# BMS_Adapter_Segment_rev1.net
KiCad netlist of a schematic drawn in EAGLE
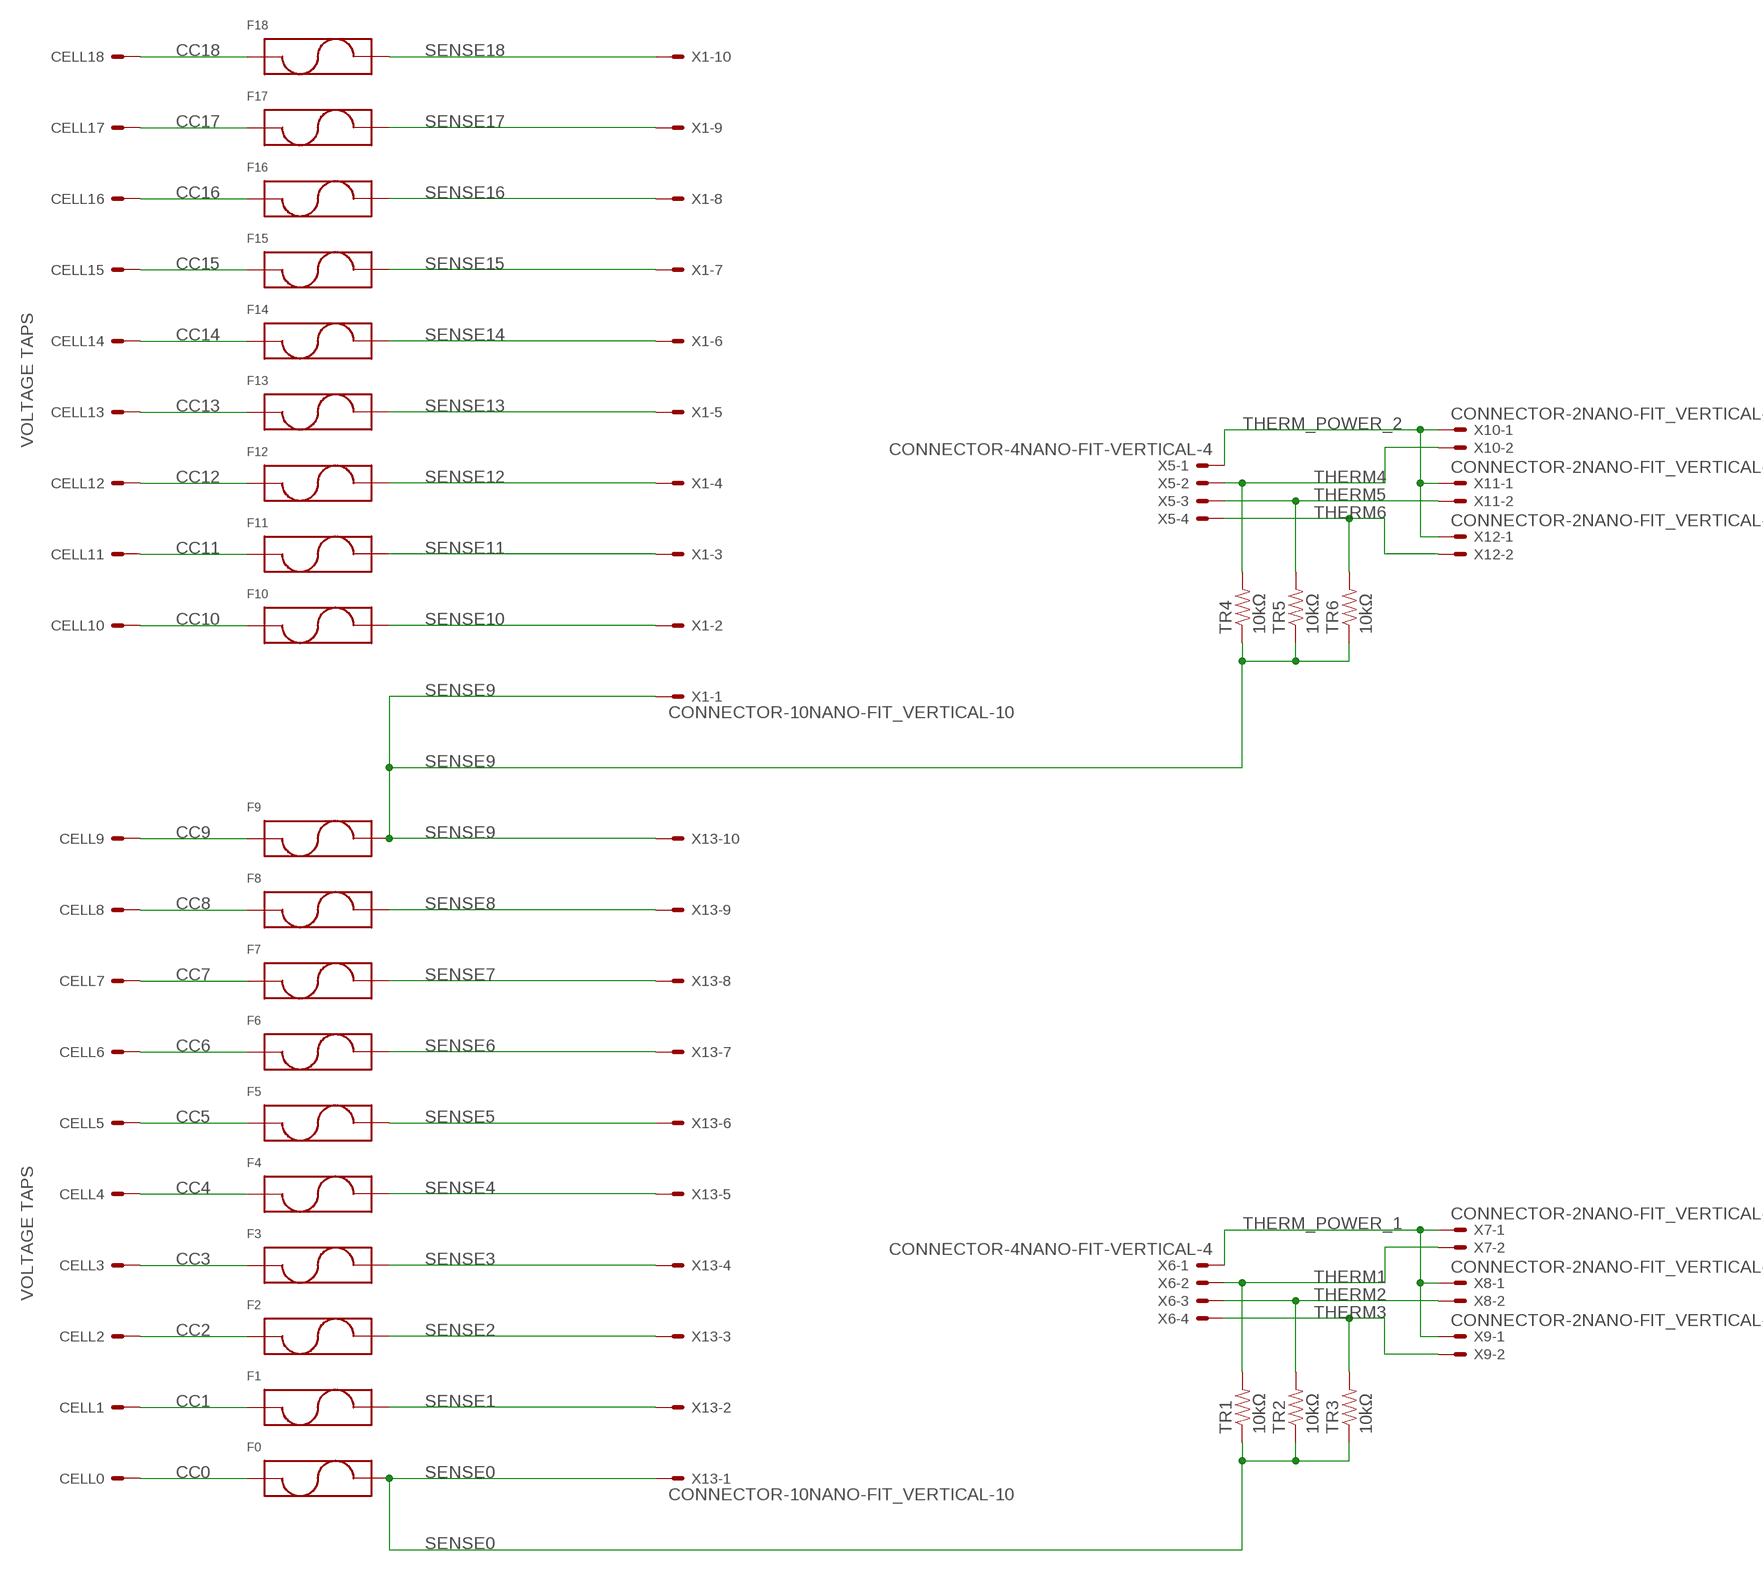
[diagram p0: schematic, sheet 1]

(export (version "E")
  (design (tool "Eeschema 10.0.6"))
  (components
    (comp (ref "CELL0")
      (value "BATTERY_SPRING_KEYSTONE5222")
      (footprint "eagle-import:KEYSTONE5222")
      (libsource (lib "eagle-import") (part "BATTERY_SPRING_KEYSTONE5222"))
    )
    (comp (ref "CELL1")
      (value "BATTERY_SPRING_KEYSTONE5222")
      (footprint "eagle-import:KEYSTONE5222")
      (libsource (lib "eagle-import") (part "BATTERY_SPRING_KEYSTONE5222"))
    )
    (comp (ref "CELL2")
      (value "BATTERY_SPRING_KEYSTONE5222")
      (footprint "eagle-import:KEYSTONE5222")
      (libsource (lib "eagle-import") (part "BATTERY_SPRING_KEYSTONE5222"))
    )
    (comp (ref "CELL3")
      (value "BATTERY_SPRING_KEYSTONE5222")
      (footprint "eagle-import:KEYSTONE5222")
      (libsource (lib "eagle-import") (part "BATTERY_SPRING_KEYSTONE5222"))
    )
    (comp (ref "CELL4")
      (value "BATTERY_SPRING_KEYSTONE5222")
      (footprint "eagle-import:KEYSTONE5222")
      (libsource (lib "eagle-import") (part "BATTERY_SPRING_KEYSTONE5222"))
    )
    (comp (ref "CELL5")
      (value "BATTERY_SPRING_KEYSTONE5222")
      (footprint "eagle-import:KEYSTONE5222")
      (libsource (lib "eagle-import") (part "BATTERY_SPRING_KEYSTONE5222"))
    )
    (comp (ref "CELL6")
      (value "BATTERY_SPRING_KEYSTONE5222")
      (footprint "eagle-import:KEYSTONE5222")
      (libsource (lib "eagle-import") (part "BATTERY_SPRING_KEYSTONE5222"))
    )
    (comp (ref "CELL7")
      (value "BATTERY_SPRING_KEYSTONE5222")
      (footprint "eagle-import:KEYSTONE5222")
      (libsource (lib "eagle-import") (part "BATTERY_SPRING_KEYSTONE5222"))
    )
    (comp (ref "CELL8")
      (value "BATTERY_SPRING_KEYSTONE5222")
      (footprint "eagle-import:KEYSTONE5222")
      (libsource (lib "eagle-import") (part "BATTERY_SPRING_KEYSTONE5222"))
    )
    (comp (ref "CELL9")
      (value "BATTERY_SPRING_KEYSTONE5222")
      (footprint "eagle-import:KEYSTONE5222")
      (libsource (lib "eagle-import") (part "BATTERY_SPRING_KEYSTONE5222"))
    )
    (comp (ref "CELL10")
      (value "BATTERY_SPRING_KEYSTONE5222")
      (footprint "eagle-import:KEYSTONE5222")
      (libsource (lib "eagle-import") (part "BATTERY_SPRING_KEYSTONE5222"))
    )
    (comp (ref "CELL11")
      (value "BATTERY_SPRING_KEYSTONE5222")
      (footprint "eagle-import:KEYSTONE5222")
      (libsource (lib "eagle-import") (part "BATTERY_SPRING_KEYSTONE5222"))
    )
    (comp (ref "CELL12")
      (value "BATTERY_SPRING_KEYSTONE5222")
      (footprint "eagle-import:KEYSTONE5222")
      (libsource (lib "eagle-import") (part "BATTERY_SPRING_KEYSTONE5222"))
    )
    (comp (ref "CELL13")
      (value "BATTERY_SPRING_KEYSTONE5222")
      (footprint "eagle-import:KEYSTONE5222")
      (libsource (lib "eagle-import") (part "BATTERY_SPRING_KEYSTONE5222"))
    )
    (comp (ref "CELL14")
      (value "BATTERY_SPRING_KEYSTONE5222")
      (footprint "eagle-import:KEYSTONE5222")
      (libsource (lib "eagle-import") (part "BATTERY_SPRING_KEYSTONE5222"))
    )
    (comp (ref "CELL15")
      (value "BATTERY_SPRING_KEYSTONE5222")
      (footprint "eagle-import:KEYSTONE5222")
      (libsource (lib "eagle-import") (part "BATTERY_SPRING_KEYSTONE5222"))
    )
    (comp (ref "CELL16")
      (value "BATTERY_SPRING_KEYSTONE5222")
      (footprint "eagle-import:KEYSTONE5222")
      (libsource (lib "eagle-import") (part "BATTERY_SPRING_KEYSTONE5222"))
    )
    (comp (ref "CELL17")
      (value "BATTERY_SPRING_KEYSTONE5222")
      (footprint "eagle-import:KEYSTONE5222")
      (libsource (lib "eagle-import") (part "BATTERY_SPRING_KEYSTONE5222"))
    )
    (comp (ref "CELL18")
      (value "BATTERY_SPRING_KEYSTONE5222")
      (footprint "eagle-import:KEYSTONE5222")
      (libsource (lib "eagle-import") (part "BATTERY_SPRING_KEYSTONE5222"))
    )
    (comp (ref "F0")
      (value "FUSE_OMF_250")
      (footprint "eagle-import:OMF_250")
      (libsource (lib "eagle-import") (part "FUSE_OMF_250"))
    )
    (comp (ref "F1")
      (value "FUSE_OMF_250")
      (footprint "eagle-import:OMF_250")
      (libsource (lib "eagle-import") (part "FUSE_OMF_250"))
    )
    (comp (ref "F2")
      (value "FUSE_OMF_250")
      (footprint "eagle-import:OMF_250")
      (libsource (lib "eagle-import") (part "FUSE_OMF_250"))
    )
    (comp (ref "F3")
      (value "FUSE_OMF_250")
      (footprint "eagle-import:OMF_250")
      (libsource (lib "eagle-import") (part "FUSE_OMF_250"))
    )
    (comp (ref "F4")
      (value "FUSE_OMF_250")
      (footprint "eagle-import:OMF_250")
      (libsource (lib "eagle-import") (part "FUSE_OMF_250"))
    )
    (comp (ref "F5")
      (value "FUSE_OMF_250")
      (footprint "eagle-import:OMF_250")
      (libsource (lib "eagle-import") (part "FUSE_OMF_250"))
    )
    (comp (ref "F6")
      (value "FUSE_OMF_250")
      (footprint "eagle-import:OMF_250")
      (libsource (lib "eagle-import") (part "FUSE_OMF_250"))
    )
    (comp (ref "F7")
      (value "FUSE_OMF_250")
      (footprint "eagle-import:OMF_250")
      (libsource (lib "eagle-import") (part "FUSE_OMF_250"))
    )
    (comp (ref "F8")
      (value "FUSE_OMF_250")
      (footprint "eagle-import:OMF_250")
      (libsource (lib "eagle-import") (part "FUSE_OMF_250"))
    )
    (comp (ref "F9")
      (value "FUSE_OMF_250")
      (footprint "eagle-import:OMF_250")
      (libsource (lib "eagle-import") (part "FUSE_OMF_250"))
    )
    (comp (ref "F10")
      (value "FUSE_OMF_250")
      (footprint "eagle-import:OMF_250")
      (libsource (lib "eagle-import") (part "FUSE_OMF_250"))
    )
    (comp (ref "F11")
      (value "FUSE_OMF_250")
      (footprint "eagle-import:OMF_250")
      (libsource (lib "eagle-import") (part "FUSE_OMF_250"))
    )
    (comp (ref "F12")
      (value "FUSE_OMF_250")
      (footprint "eagle-import:OMF_250")
      (libsource (lib "eagle-import") (part "FUSE_OMF_250"))
    )
    (comp (ref "F13")
      (value "FUSE_OMF_250")
      (footprint "eagle-import:OMF_250")
      (libsource (lib "eagle-import") (part "FUSE_OMF_250"))
    )
    (comp (ref "F14")
      (value "FUSE_OMF_250")
      (footprint "eagle-import:OMF_250")
      (libsource (lib "eagle-import") (part "FUSE_OMF_250"))
    )
    (comp (ref "F15")
      (value "FUSE_OMF_250")
      (footprint "eagle-import:OMF_250")
      (libsource (lib "eagle-import") (part "FUSE_OMF_250"))
    )
    (comp (ref "F16")
      (value "FUSE_OMF_250")
      (footprint "eagle-import:OMF_250")
      (libsource (lib "eagle-import") (part "FUSE_OMF_250"))
    )
    (comp (ref "F17")
      (value "FUSE_OMF_250")
      (footprint "eagle-import:OMF_250")
      (libsource (lib "eagle-import") (part "FUSE_OMF_250"))
    )
    (comp (ref "F18")
      (value "FUSE_OMF_250")
      (footprint "eagle-import:OMF_250")
      (libsource (lib "eagle-import") (part "FUSE_OMF_250"))
    )
    (comp (ref "TR1")
      (value "10kΩ")
      (footprint "eagle-import:0805")
      (libsource (lib "eagle-import") (part "RESISTOR0805-RES"))
    )
    (comp (ref "TR2")
      (value "10kΩ")
      (footprint "eagle-import:0805")
      (libsource (lib "eagle-import") (part "RESISTOR0805-RES"))
    )
    (comp (ref "TR3")
      (value "10kΩ")
      (footprint "eagle-import:0805")
      (libsource (lib "eagle-import") (part "RESISTOR0805-RES"))
    )
    (comp (ref "TR4")
      (value "10kΩ")
      (footprint "eagle-import:0805")
      (libsource (lib "eagle-import") (part "RESISTOR0805-RES"))
    )
    (comp (ref "TR5")
      (value "10kΩ")
      (footprint "eagle-import:0805")
      (libsource (lib "eagle-import") (part "RESISTOR0805-RES"))
    )
    (comp (ref "TR6")
      (value "10kΩ")
      (footprint "eagle-import:0805")
      (libsource (lib "eagle-import") (part "RESISTOR0805-RES"))
    )
    (comp (ref "X1")
      (value "CONNECTOR-10NANO-FIT_VERTICAL-10")
      (footprint "eagle-import:NANO-FIT_VERTICAL-10")
      (libsource (lib "eagle-import") (part "CONNECTOR-10NANO-FIT_VERTICAL-10"))
    )
    (comp (ref "X5")
      (value "CONNECTOR-4NANO-FIT-VERTICAL-4")
      (footprint "eagle-import:NANO-FIT_VERTICAL-4")
      (libsource (lib "eagle-import") (part "CONNECTOR-4NANO-FIT-VERTICAL-4"))
    )
    (comp (ref "X6")
      (value "CONNECTOR-4NANO-FIT-VERTICAL-4")
      (footprint "eagle-import:NANO-FIT_VERTICAL-4")
      (libsource (lib "eagle-import") (part "CONNECTOR-4NANO-FIT-VERTICAL-4"))
    )
    (comp (ref "X7")
      (value "CONNECTOR-2NANO-FIT_VERTICAL-2")
      (footprint "eagle-import:NANO-FIT_VERTICAL-2")
      (libsource (lib "eagle-import") (part "CONNECTOR-2NANO-FIT_VERTICAL-2"))
    )
    (comp (ref "X8")
      (value "CONNECTOR-2NANO-FIT_VERTICAL-2")
      (footprint "eagle-import:NANO-FIT_VERTICAL-2")
      (libsource (lib "eagle-import") (part "CONNECTOR-2NANO-FIT_VERTICAL-2"))
    )
    (comp (ref "X9")
      (value "CONNECTOR-2NANO-FIT_VERTICAL-2")
      (footprint "eagle-import:NANO-FIT_VERTICAL-2")
      (libsource (lib "eagle-import") (part "CONNECTOR-2NANO-FIT_VERTICAL-2"))
    )
    (comp (ref "X10")
      (value "CONNECTOR-2NANO-FIT_VERTICAL-2")
      (footprint "eagle-import:NANO-FIT_VERTICAL-2")
      (libsource (lib "eagle-import") (part "CONNECTOR-2NANO-FIT_VERTICAL-2"))
    )
    (comp (ref "X11")
      (value "CONNECTOR-2NANO-FIT_VERTICAL-2")
      (footprint "eagle-import:NANO-FIT_VERTICAL-2")
      (libsource (lib "eagle-import") (part "CONNECTOR-2NANO-FIT_VERTICAL-2"))
    )
    (comp (ref "X12")
      (value "CONNECTOR-2NANO-FIT_VERTICAL-2")
      (footprint "eagle-import:NANO-FIT_VERTICAL-2")
      (libsource (lib "eagle-import") (part "CONNECTOR-2NANO-FIT_VERTICAL-2"))
    )
    (comp (ref "X13")
      (value "CONNECTOR-10NANO-FIT_VERTICAL-10")
      (footprint "eagle-import:NANO-FIT_VERTICAL-10")
      (libsource (lib "eagle-import") (part "CONNECTOR-10NANO-FIT_VERTICAL-10"))
    )
  )
  (nets
    (net (code "1") (name "/CC0") (class "Default")
      (node (ref "CELL0") (pin "P$1") (pinfunction "S_P$1") (pintype "passive"))
      (node (ref "F0") (pin "P$1") (pinfunction "P1_P$1") (pintype "bidirectional"))
    )
    (net (code "2") (name "/CC1") (class "Default")
      (node (ref "CELL1") (pin "P$1") (pinfunction "S_P$1") (pintype "passive"))
      (node (ref "F1") (pin "P$1") (pinfunction "P1_P$1") (pintype "bidirectional"))
    )
    (net (code "3") (name "/CC2") (class "Default")
      (node (ref "CELL2") (pin "P$1") (pinfunction "S_P$1") (pintype "passive"))
      (node (ref "F2") (pin "P$1") (pinfunction "P1_P$1") (pintype "bidirectional"))
    )
    (net (code "4") (name "/CC3") (class "Default")
      (node (ref "CELL3") (pin "P$1") (pinfunction "S_P$1") (pintype "passive"))
      (node (ref "F3") (pin "P$1") (pinfunction "P1_P$1") (pintype "bidirectional"))
    )
    (net (code "5") (name "/CC4") (class "Default")
      (node (ref "CELL4") (pin "P$1") (pinfunction "S_P$1") (pintype "passive"))
      (node (ref "F4") (pin "P$1") (pinfunction "P1_P$1") (pintype "bidirectional"))
    )
    (net (code "6") (name "/CC5") (class "Default")
      (node (ref "CELL5") (pin "P$1") (pinfunction "S_P$1") (pintype "passive"))
      (node (ref "F5") (pin "P$1") (pinfunction "P1_P$1") (pintype "bidirectional"))
    )
    (net (code "7") (name "/CC6") (class "Default")
      (node (ref "CELL6") (pin "P$1") (pinfunction "S_P$1") (pintype "passive"))
      (node (ref "F6") (pin "P$1") (pinfunction "P1_P$1") (pintype "bidirectional"))
    )
    (net (code "8") (name "/CC7") (class "Default")
      (node (ref "CELL7") (pin "P$1") (pinfunction "S_P$1") (pintype "passive"))
      (node (ref "F7") (pin "P$1") (pinfunction "P1_P$1") (pintype "bidirectional"))
    )
    (net (code "9") (name "/CC8") (class "Default")
      (node (ref "CELL8") (pin "P$1") (pinfunction "S_P$1") (pintype "passive"))
      (node (ref "F8") (pin "P$1") (pinfunction "P1_P$1") (pintype "bidirectional"))
    )
    (net (code "10") (name "/CC9") (class "Default")
      (node (ref "CELL9") (pin "P$1") (pinfunction "S_P$1") (pintype "passive"))
      (node (ref "F9") (pin "P$1") (pinfunction "P1_P$1") (pintype "bidirectional"))
    )
    (net (code "11") (name "/CC10") (class "Default")
      (node (ref "CELL10") (pin "P$1") (pinfunction "S_P$1") (pintype "passive"))
      (node (ref "F10") (pin "P$1") (pinfunction "P1_P$1") (pintype "bidirectional"))
    )
    (net (code "12") (name "/CC11") (class "Default")
      (node (ref "CELL11") (pin "P$1") (pinfunction "S_P$1") (pintype "passive"))
      (node (ref "F11") (pin "P$1") (pinfunction "P1_P$1") (pintype "bidirectional"))
    )
    (net (code "13") (name "/CC12") (class "Default")
      (node (ref "CELL12") (pin "P$1") (pinfunction "S_P$1") (pintype "passive"))
      (node (ref "F12") (pin "P$1") (pinfunction "P1_P$1") (pintype "bidirectional"))
    )
    (net (code "14") (name "/CC13") (class "Default")
      (node (ref "CELL13") (pin "P$1") (pinfunction "S_P$1") (pintype "passive"))
      (node (ref "F13") (pin "P$1") (pinfunction "P1_P$1") (pintype "bidirectional"))
    )
    (net (code "15") (name "/CC14") (class "Default")
      (node (ref "CELL14") (pin "P$1") (pinfunction "S_P$1") (pintype "passive"))
      (node (ref "F14") (pin "P$1") (pinfunction "P1_P$1") (pintype "bidirectional"))
    )
    (net (code "16") (name "/CC15") (class "Default")
      (node (ref "CELL15") (pin "P$1") (pinfunction "S_P$1") (pintype "passive"))
      (node (ref "F15") (pin "P$1") (pinfunction "P1_P$1") (pintype "bidirectional"))
    )
    (net (code "17") (name "/CC16") (class "Default")
      (node (ref "CELL16") (pin "P$1") (pinfunction "S_P$1") (pintype "passive"))
      (node (ref "F16") (pin "P$1") (pinfunction "P1_P$1") (pintype "bidirectional"))
    )
    (net (code "18") (name "/CC17") (class "Default")
      (node (ref "CELL17") (pin "P$1") (pinfunction "S_P$1") (pintype "passive"))
      (node (ref "F17") (pin "P$1") (pinfunction "P1_P$1") (pintype "bidirectional"))
    )
    (net (code "19") (name "/CC18") (class "Default")
      (node (ref "CELL18") (pin "P$1") (pinfunction "S_P$1") (pintype "passive"))
      (node (ref "F18") (pin "P$1") (pinfunction "P1_P$1") (pintype "bidirectional"))
    )
    (net (code "20") (name "/SENSE0") (class "Default")
      (node (ref "F0") (pin "P$2") (pinfunction "P2_P$2") (pintype "bidirectional"))
      (node (ref "TR1") (pin "1") (pinfunction "1_1") (pintype "passive"))
      (node (ref "TR2") (pin "1") (pinfunction "1_1") (pintype "passive"))
      (node (ref "TR3") (pin "1") (pinfunction "1_1") (pintype "passive"))
      (node (ref "X13") (pin "P$1") (pinfunction "S_P$1") (pintype "passive"))
    )
    (net (code "21") (name "/SENSE1") (class "Default")
      (node (ref "F1") (pin "P$2") (pinfunction "P2_P$2") (pintype "bidirectional"))
      (node (ref "X13") (pin "P$2") (pinfunction "S_P$2") (pintype "passive"))
    )
    (net (code "22") (name "/SENSE2") (class "Default")
      (node (ref "F2") (pin "P$2") (pinfunction "P2_P$2") (pintype "bidirectional"))
      (node (ref "X13") (pin "P$3") (pinfunction "S_P$3") (pintype "passive"))
    )
    (net (code "23") (name "/SENSE3") (class "Default")
      (node (ref "F3") (pin "P$2") (pinfunction "P2_P$2") (pintype "bidirectional"))
      (node (ref "X13") (pin "P$4") (pinfunction "S_P$4") (pintype "passive"))
    )
    (net (code "24") (name "/SENSE4") (class "Default")
      (node (ref "F4") (pin "P$2") (pinfunction "P2_P$2") (pintype "bidirectional"))
      (node (ref "X13") (pin "P$5") (pinfunction "S_P$5") (pintype "passive"))
    )
    (net (code "25") (name "/SENSE5") (class "Default")
      (node (ref "F5") (pin "P$2") (pinfunction "P2_P$2") (pintype "bidirectional"))
      (node (ref "X13") (pin "P$6") (pinfunction "S_P$6") (pintype "passive"))
    )
    (net (code "26") (name "/SENSE6") (class "Default")
      (node (ref "F6") (pin "P$2") (pinfunction "P2_P$2") (pintype "bidirectional"))
      (node (ref "X13") (pin "P$7") (pinfunction "S_P$7") (pintype "passive"))
    )
    (net (code "27") (name "/SENSE7") (class "Default")
      (node (ref "F7") (pin "P$2") (pinfunction "P2_P$2") (pintype "bidirectional"))
      (node (ref "X13") (pin "P$8") (pinfunction "S_P$8") (pintype "passive"))
    )
    (net (code "28") (name "/SENSE8") (class "Default")
      (node (ref "F8") (pin "P$2") (pinfunction "P2_P$2") (pintype "bidirectional"))
      (node (ref "X13") (pin "P$9") (pinfunction "S_P$9") (pintype "passive"))
    )
    (net (code "29") (name "/SENSE9") (class "Default")
      (node (ref "F9") (pin "P$2") (pinfunction "P2_P$2") (pintype "bidirectional"))
      (node (ref "TR4") (pin "1") (pinfunction "1_1") (pintype "passive"))
      (node (ref "TR5") (pin "1") (pinfunction "1_1") (pintype "passive"))
      (node (ref "TR6") (pin "1") (pinfunction "1_1") (pintype "passive"))
      (node (ref "X1") (pin "P$1") (pinfunction "S_P$1") (pintype "passive"))
      (node (ref "X13") (pin "P$10") (pinfunction "S_P$10") (pintype "passive"))
    )
    (net (code "30") (name "/SENSE10") (class "Default")
      (node (ref "F10") (pin "P$2") (pinfunction "P2_P$2") (pintype "bidirectional"))
      (node (ref "X1") (pin "P$2") (pinfunction "S_P$2") (pintype "passive"))
    )
    (net (code "31") (name "/SENSE11") (class "Default")
      (node (ref "F11") (pin "P$2") (pinfunction "P2_P$2") (pintype "bidirectional"))
      (node (ref "X1") (pin "P$3") (pinfunction "S_P$3") (pintype "passive"))
    )
    (net (code "32") (name "/SENSE12") (class "Default")
      (node (ref "F12") (pin "P$2") (pinfunction "P2_P$2") (pintype "bidirectional"))
      (node (ref "X1") (pin "P$4") (pinfunction "S_P$4") (pintype "passive"))
    )
    (net (code "33") (name "/SENSE13") (class "Default")
      (node (ref "F13") (pin "P$2") (pinfunction "P2_P$2") (pintype "bidirectional"))
      (node (ref "X1") (pin "P$5") (pinfunction "S_P$5") (pintype "passive"))
    )
    (net (code "34") (name "/SENSE14") (class "Default")
      (node (ref "F14") (pin "P$2") (pinfunction "P2_P$2") (pintype "bidirectional"))
      (node (ref "X1") (pin "P$6") (pinfunction "S_P$6") (pintype "passive"))
    )
    (net (code "35") (name "/SENSE15") (class "Default")
      (node (ref "F15") (pin "P$2") (pinfunction "P2_P$2") (pintype "bidirectional"))
      (node (ref "X1") (pin "P$7") (pinfunction "S_P$7") (pintype "passive"))
    )
    (net (code "36") (name "/SENSE16") (class "Default")
      (node (ref "F16") (pin "P$2") (pinfunction "P2_P$2") (pintype "bidirectional"))
      (node (ref "X1") (pin "P$8") (pinfunction "S_P$8") (pintype "passive"))
    )
    (net (code "37") (name "/SENSE17") (class "Default")
      (node (ref "F17") (pin "P$2") (pinfunction "P2_P$2") (pintype "bidirectional"))
      (node (ref "X1") (pin "P$9") (pinfunction "S_P$9") (pintype "passive"))
    )
    (net (code "38") (name "/SENSE18") (class "Default")
      (node (ref "F18") (pin "P$2") (pinfunction "P2_P$2") (pintype "bidirectional"))
      (node (ref "X1") (pin "P$10") (pinfunction "S_P$10") (pintype "passive"))
    )
    (net (code "39") (name "/THERM1") (class "Default")
      (node (ref "TR1") (pin "2") (pinfunction "2_2") (pintype "passive"))
      (node (ref "X6") (pin "P$2") (pinfunction "S_P$2") (pintype "passive"))
      (node (ref "X7") (pin "P$2") (pinfunction "S_P$2") (pintype "passive"))
    )
    (net (code "40") (name "/THERM2") (class "Default")
      (node (ref "TR2") (pin "2") (pinfunction "2_2") (pintype "passive"))
      (node (ref "X6") (pin "P$3") (pinfunction "S_P$3") (pintype "passive"))
      (node (ref "X8") (pin "P$2") (pinfunction "S_P$2") (pintype "passive"))
    )
    (net (code "41") (name "/THERM3") (class "Default")
      (node (ref "TR3") (pin "2") (pinfunction "2_2") (pintype "passive"))
      (node (ref "X6") (pin "P$4") (pinfunction "S_P$4") (pintype "passive"))
      (node (ref "X9") (pin "P$2") (pinfunction "S_P$2") (pintype "passive"))
    )
    (net (code "42") (name "/THERM4") (class "Default")
      (node (ref "TR4") (pin "2") (pinfunction "2_2") (pintype "passive"))
      (node (ref "X10") (pin "P$2") (pinfunction "S_P$2") (pintype "passive"))
      (node (ref "X5") (pin "P$2") (pinfunction "S_P$2") (pintype "passive"))
    )
    (net (code "43") (name "/THERM5") (class "Default")
      (node (ref "TR5") (pin "2") (pinfunction "2_2") (pintype "passive"))
      (node (ref "X11") (pin "P$2") (pinfunction "S_P$2") (pintype "passive"))
      (node (ref "X5") (pin "P$3") (pinfunction "S_P$3") (pintype "passive"))
    )
    (net (code "44") (name "/THERM6") (class "Default")
      (node (ref "TR6") (pin "2") (pinfunction "2_2") (pintype "passive"))
      (node (ref "X12") (pin "P$2") (pinfunction "S_P$2") (pintype "passive"))
      (node (ref "X5") (pin "P$4") (pinfunction "S_P$4") (pintype "passive"))
    )
    (net (code "45") (name "/THERM_POWER_1") (class "Default")
      (node (ref "X6") (pin "P$1") (pinfunction "S_P$1") (pintype "passive"))
      (node (ref "X7") (pin "P$1") (pinfunction "S_P$1") (pintype "passive"))
      (node (ref "X8") (pin "P$1") (pinfunction "S_P$1") (pintype "passive"))
      (node (ref "X9") (pin "P$1") (pinfunction "S_P$1") (pintype "passive"))
    )
    (net (code "46") (name "/THERM_POWER_2") (class "Default")
      (node (ref "X10") (pin "P$1") (pinfunction "S_P$1") (pintype "passive"))
      (node (ref "X11") (pin "P$1") (pinfunction "S_P$1") (pintype "passive"))
      (node (ref "X12") (pin "P$1") (pinfunction "S_P$1") (pintype "passive"))
      (node (ref "X5") (pin "P$1") (pinfunction "S_P$1") (pintype "passive"))
    )
  )
)
